# OpenHPI_Embedded_Smart_Home_RPi_Board.net
KiCad netlist of a schematic drawn in EAGLE
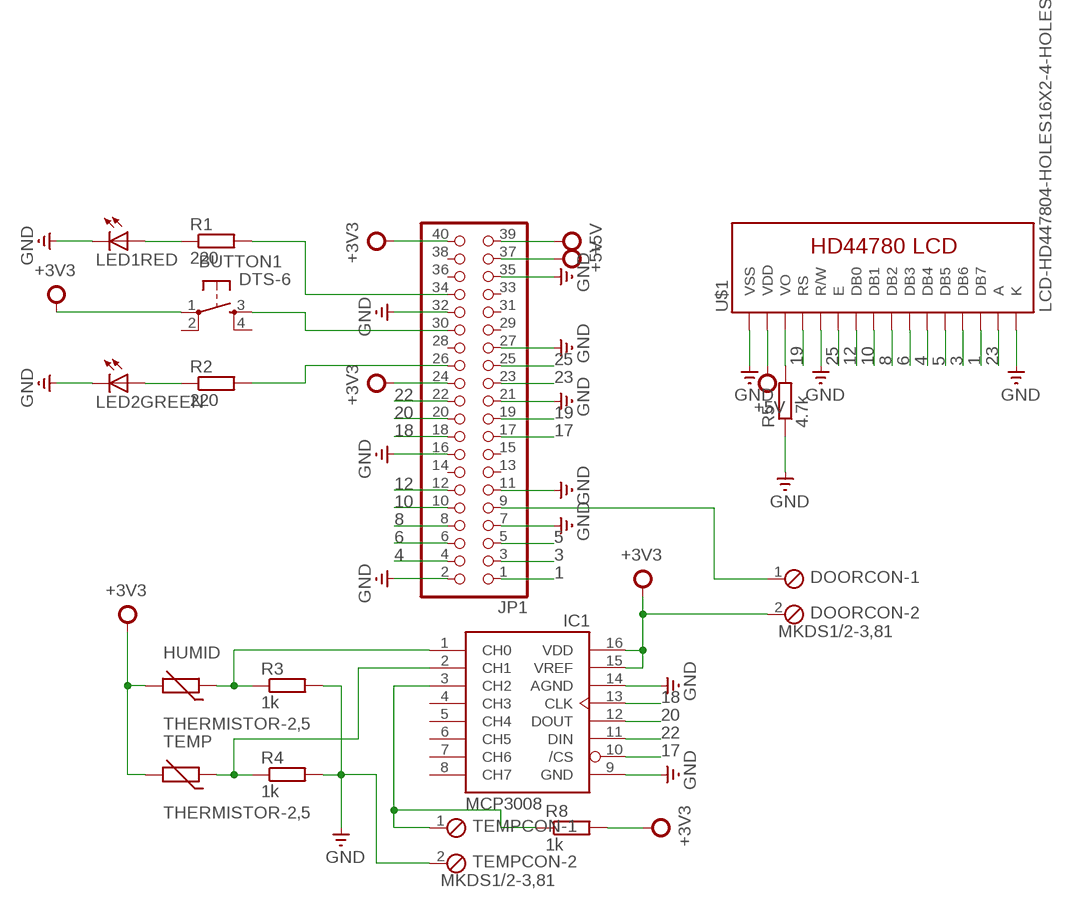
[diagram p0: schematic, sheet 1]

(export (version "E")
  (design (tool "Eeschema 10.0.6"))
  (components
    (comp (ref "BUTTON1")
      (value "DTS-6")
      (footprint "eagle-import:DTS-6")
      (libsource (lib "eagle-import") (part "DTS-6"))
    )
    (comp (ref "DOORCON")
      (value "MKDS1/2-3,81")
      (footprint "eagle-import:2POL381")
      (libsource (lib "eagle-import") (part "MKDS1/2-3,81"))
    )
    (comp (ref "HUMID")
      (value "THERMISTOR-2,5")
      (footprint "eagle-import:RS-2,5")
      (libsource (lib "eagle-import") (part "THERMISTOR-2,5"))
    )
    (comp (ref "IC1")
      (value "MCP3008")
      (footprint "eagle-import:DIL16")
      (libsource (lib "eagle-import") (part "MCP3008"))
    )
    (comp (ref "JP1")
      (value "PINHD-2X20")
      (footprint "eagle-import:2X20")
      (libsource (lib "eagle-import") (part "PINHD-2X20"))
    )
    (comp (ref "LED1RED")
      (value "LED5MM")
      (footprint "eagle-import:LED5MM")
      (libsource (lib "eagle-import") (part "LED5MM"))
    )
    (comp (ref "LED2GREEN")
      (value "LED5MM")
      (footprint "eagle-import:LED5MM")
      (libsource (lib "eagle-import") (part "LED5MM"))
    )
    (comp (ref "R1")
      (value "220")
      (footprint "eagle-import:0207_7")
      (libsource (lib "eagle-import") (part "R-EU_0207/7"))
    )
    (comp (ref "R2")
      (value "220")
      (footprint "eagle-import:0207_7")
      (libsource (lib "eagle-import") (part "R-EU_0207/7"))
    )
    (comp (ref "R3")
      (value "1k")
      (footprint "eagle-import:0207_7")
      (libsource (lib "eagle-import") (part "R-EU_0207/7"))
    )
    (comp (ref "R4")
      (value "1k")
      (footprint "eagle-import:0207_7")
      (libsource (lib "eagle-import") (part "R-EU_0207/7"))
    )
    (comp (ref "R5")
      (value "4.7k")
      (footprint "eagle-import:0207_7")
      (libsource (lib "eagle-import") (part "R-EU_0207/7"))
    )
    (comp (ref "R8")
      (value "1k")
      (footprint "eagle-import:0207_7")
      (libsource (lib "eagle-import") (part "R-EU_0207/7"))
    )
    (comp (ref "TEMP")
      (value "THERMISTOR-2,5")
      (footprint "eagle-import:RS-2,5")
      (libsource (lib "eagle-import") (part "THERMISTOR-2,5"))
    )
    (comp (ref "TEMPCON")
      (value "MKDS1/2-3,81")
      (footprint "eagle-import:2POL381")
      (libsource (lib "eagle-import") (part "MKDS1/2-3,81"))
    )
    (comp (ref "U$1")
      (value "LCD-HD447804-HOLES16X2-4-HOLES")
      (footprint "eagle-import:LCD-16X2-4HOLES")
      (libsource (lib "eagle-import") (part "LCD-HD4478016X2-4-HOLES4-HOLES"))
    )
  )
  (nets
    (net (code "1") (name "+3V3") (class "Default")
      (node (ref "BUTTON1") (pin "1") (pinfunction "1_1") (pintype "passive"))
      (node (ref "DOORCON") (pin "2") (pinfunction "1_2") (pintype "passive"))
      (node (ref "HUMID") (pin "2") (pinfunction "2_2") (pintype "passive"))
      (node (ref "IC1") (pin "15") (pinfunction "VREF_15") (pintype "input"))
      (node (ref "IC1") (pin "16") (pinfunction "VDD_16") (pintype "power_in"))
      (node (ref "JP1") (pin "24") (pinfunction "24_24") (pintype "passive"))
      (node (ref "JP1") (pin "40") (pinfunction "40_40") (pintype "passive"))
      (node (ref "R8") (pin "2") (pinfunction "2_2") (pintype "passive"))
      (node (ref "TEMP") (pin "2") (pinfunction "2_2") (pintype "passive"))
    )
    (net (code "2") (name "+5V") (class "Default")
      (node (ref "JP1") (pin "37") (pinfunction "37_37") (pintype "passive"))
      (node (ref "JP1") (pin "39") (pinfunction "39_39") (pintype "passive"))
      (node (ref "U$1") (pin "2") (pinfunction "VDD_2") (pintype "power_in"))
    )
    (net (code "3") (name "/1") (class "Default")
      (node (ref "JP1") (pin "1") (pinfunction "1_1") (pintype "passive"))
      (node (ref "U$1") (pin "14") (pinfunction "DB7_14") (pintype "bidirectional"))
    )
    (net (code "4") (name "/3") (class "Default")
      (node (ref "JP1") (pin "3") (pinfunction "3_3") (pintype "passive"))
      (node (ref "U$1") (pin "13") (pinfunction "DB6_13") (pintype "bidirectional"))
    )
    (net (code "5") (name "/4") (class "Default")
      (node (ref "JP1") (pin "4") (pinfunction "4_4") (pintype "passive"))
      (node (ref "U$1") (pin "11") (pinfunction "DB4_11") (pintype "bidirectional"))
    )
    (net (code "6") (name "/5") (class "Default")
      (node (ref "JP1") (pin "5") (pinfunction "5_5") (pintype "passive"))
      (node (ref "U$1") (pin "12") (pinfunction "DB5_12") (pintype "bidirectional"))
    )
    (net (code "7") (name "/6") (class "Default")
      (node (ref "JP1") (pin "6") (pinfunction "6_6") (pintype "passive"))
      (node (ref "U$1") (pin "10") (pinfunction "DB3_10") (pintype "bidirectional"))
    )
    (net (code "8") (name "/8") (class "Default")
      (node (ref "JP1") (pin "8") (pinfunction "8_8") (pintype "passive"))
      (node (ref "U$1") (pin "9") (pinfunction "DB2_9") (pintype "bidirectional"))
    )
    (net (code "9") (name "/10") (class "Default")
      (node (ref "JP1") (pin "10") (pinfunction "10_10") (pintype "passive"))
      (node (ref "U$1") (pin "8") (pinfunction "DB1_8") (pintype "bidirectional"))
    )
    (net (code "10") (name "/12") (class "Default")
      (node (ref "JP1") (pin "12") (pinfunction "12_12") (pintype "passive"))
      (node (ref "U$1") (pin "7") (pinfunction "DB0_7") (pintype "bidirectional"))
    )
    (net (code "11") (name "/17") (class "Default")
      (node (ref "IC1") (pin "10") (pinfunction "/CS_10") (pintype "input"))
      (node (ref "JP1") (pin "17") (pinfunction "17_17") (pintype "passive"))
    )
    (net (code "12") (name "/18") (class "Default")
      (node (ref "IC1") (pin "13") (pinfunction "CLK_13") (pintype "input"))
      (node (ref "JP1") (pin "18") (pinfunction "18_18") (pintype "passive"))
    )
    (net (code "13") (name "/19") (class "Default")
      (node (ref "JP1") (pin "19") (pinfunction "19_19") (pintype "passive"))
      (node (ref "U$1") (pin "4") (pinfunction "RS_4") (pintype "input"))
    )
    (net (code "14") (name "/20") (class "Default")
      (node (ref "IC1") (pin "12") (pinfunction "DOUT_12") (pintype "output"))
      (node (ref "JP1") (pin "20") (pinfunction "20_20") (pintype "passive"))
    )
    (net (code "15") (name "/22") (class "Default")
      (node (ref "IC1") (pin "11") (pinfunction "DIN_11") (pintype "input"))
      (node (ref "JP1") (pin "22") (pinfunction "22_22") (pintype "passive"))
    )
    (net (code "16") (name "/23") (class "Default")
      (node (ref "JP1") (pin "23") (pinfunction "23_23") (pintype "passive"))
      (node (ref "U$1") (pin "15") (pinfunction "A_15") (pintype "power_in"))
    )
    (net (code "17") (name "/25") (class "Default")
      (node (ref "JP1") (pin "25") (pinfunction "25_25") (pintype "passive"))
      (node (ref "U$1") (pin "6") (pinfunction "E_6") (pintype "input"))
    )
    (net (code "18") (name "GND") (class "Default")
      (node (ref "IC1") (pin "14") (pinfunction "AGND_14") (pintype "power_in"))
      (node (ref "IC1") (pin "9") (pinfunction "GND_9") (pintype "power_in"))
      (node (ref "JP1") (pin "11") (pinfunction "11_11") (pintype "passive"))
      (node (ref "JP1") (pin "16") (pinfunction "16_16") (pintype "passive"))
      (node (ref "JP1") (pin "2") (pinfunction "2_2") (pintype "passive"))
      (node (ref "JP1") (pin "21") (pinfunction "21_21") (pintype "passive"))
      (node (ref "JP1") (pin "27") (pinfunction "27_27") (pintype "passive"))
      (node (ref "JP1") (pin "32") (pinfunction "32_32") (pintype "passive"))
      (node (ref "JP1") (pin "35") (pinfunction "35_35") (pintype "passive"))
      (node (ref "JP1") (pin "7") (pinfunction "7_7") (pintype "passive"))
      (node (ref "LED1RED") (pin "K") (pinfunction "C_K") (pintype "passive"))
      (node (ref "LED2GREEN") (pin "K") (pinfunction "C_K") (pintype "passive"))
      (node (ref "R3") (pin "2") (pinfunction "2_2") (pintype "passive"))
      (node (ref "R4") (pin "2") (pinfunction "2_2") (pintype "passive"))
      (node (ref "R5") (pin "1") (pinfunction "1_1") (pintype "passive"))
      (node (ref "TEMPCON") (pin "2") (pinfunction "1_2") (pintype "passive"))
      (node (ref "U$1") (pin "1") (pinfunction "VSS_1") (pintype "power_in"))
      (node (ref "U$1") (pin "16") (pinfunction "K_16") (pintype "power_in"))
      (node (ref "U$1") (pin "5") (pinfunction "R/W_5") (pintype "input"))
    )
    (net (code "19") (name "Net-(BUTTON1-Pad3)") (class "Default")
      (node (ref "BUTTON1") (pin "3") (pinfunction "3_3") (pintype "passive"))
      (node (ref "JP1") (pin "30") (pinfunction "30_30") (pintype "passive"))
    )
    (net (code "20") (name "Net-(DOORCON-Pad1)") (class "Default")
      (node (ref "DOORCON") (pin "1") (pinfunction "1_1") (pintype "passive"))
      (node (ref "JP1") (pin "9") (pinfunction "9_9") (pintype "passive"))
    )
    (net (code "21") (name "Net-(IC1-CH0)") (class "Default")
      (node (ref "HUMID") (pin "1") (pinfunction "1_1") (pintype "passive"))
      (node (ref "IC1") (pin "1") (pinfunction "CH0_1") (pintype "input"))
      (node (ref "R3") (pin "1") (pinfunction "1_1") (pintype "passive"))
    )
    (net (code "22") (name "Net-(IC1-CH1)") (class "Default")
      (node (ref "IC1") (pin "2") (pinfunction "CH1_2") (pintype "input"))
      (node (ref "R4") (pin "1") (pinfunction "1_1") (pintype "passive"))
      (node (ref "TEMP") (pin "1") (pinfunction "1_1") (pintype "passive"))
    )
    (net (code "23") (name "Net-(IC1-CH2)") (class "Default")
      (node (ref "IC1") (pin "3") (pinfunction "CH2_3") (pintype "input"))
      (node (ref "R8") (pin "1") (pinfunction "1_1") (pintype "passive"))
      (node (ref "TEMPCON") (pin "1") (pinfunction "1_1") (pintype "passive"))
    )
    (net (code "24") (name "Net-(JP1-Pad26)") (class "Default")
      (node (ref "JP1") (pin "26") (pinfunction "26_26") (pintype "passive"))
      (node (ref "R2") (pin "2") (pinfunction "2_2") (pintype "passive"))
    )
    (net (code "25") (name "Net-(JP1-Pad34)") (class "Default")
      (node (ref "JP1") (pin "34") (pinfunction "34_34") (pintype "passive"))
      (node (ref "R1") (pin "2") (pinfunction "2_2") (pintype "passive"))
    )
    (net (code "26") (name "Net-(LED1RED-PadA)") (class "Default")
      (node (ref "LED1RED") (pin "A") (pinfunction "A_A") (pintype "passive"))
      (node (ref "R1") (pin "1") (pinfunction "1_1") (pintype "passive"))
    )
    (net (code "27") (name "Net-(LED2GREEN-PadA)") (class "Default")
      (node (ref "LED2GREEN") (pin "A") (pinfunction "A_A") (pintype "passive"))
      (node (ref "R2") (pin "1") (pinfunction "1_1") (pintype "passive"))
    )
    (net (code "28") (name "Net-(U$1-VO)") (class "Default")
      (node (ref "R5") (pin "2") (pinfunction "2_2") (pintype "passive"))
      (node (ref "U$1") (pin "3") (pinfunction "VO_3") (pintype "bidirectional"))
    )
    (net (code "29") (name "unconnected-(BUTTON1-Pad2)") (class "Default")
      (node (ref "BUTTON1") (pin "2") (pinfunction "2_2") (pintype "passive"))
    )
    (net (code "30") (name "unconnected-(BUTTON1-Pad4)") (class "Default")
      (node (ref "BUTTON1") (pin "4") (pinfunction "4_4") (pintype "passive"))
    )
    (net (code "31") (name "unconnected-(IC1-CH3-Pad4)") (class "Default")
      (node (ref "IC1") (pin "4") (pinfunction "CH3_4") (pintype "input"))
    )
    (net (code "32") (name "unconnected-(IC1-CH4-Pad5)") (class "Default")
      (node (ref "IC1") (pin "5") (pinfunction "CH4_5") (pintype "input"))
    )
    (net (code "33") (name "unconnected-(IC1-CH5-Pad6)") (class "Default")
      (node (ref "IC1") (pin "6") (pinfunction "CH5_6") (pintype "input"))
    )
    (net (code "34") (name "unconnected-(IC1-CH6-Pad7)") (class "Default")
      (node (ref "IC1") (pin "7") (pinfunction "CH6_7") (pintype "input"))
    )
    (net (code "35") (name "unconnected-(IC1-CH7-Pad8)") (class "Default")
      (node (ref "IC1") (pin "8") (pinfunction "CH7_8") (pintype "input"))
    )
    (net (code "36") (name "unconnected-(JP1-Pad13)") (class "Default")
      (node (ref "JP1") (pin "13") (pinfunction "13_13") (pintype "passive"))
    )
    (net (code "37") (name "unconnected-(JP1-Pad14)") (class "Default")
      (node (ref "JP1") (pin "14") (pinfunction "14_14") (pintype "passive"))
    )
    (net (code "38") (name "unconnected-(JP1-Pad15)") (class "Default")
      (node (ref "JP1") (pin "15") (pinfunction "15_15") (pintype "passive"))
    )
    (net (code "39") (name "unconnected-(JP1-Pad28)") (class "Default")
      (node (ref "JP1") (pin "28") (pinfunction "28_28") (pintype "passive"))
    )
    (net (code "40") (name "unconnected-(JP1-Pad29)") (class "Default")
      (node (ref "JP1") (pin "29") (pinfunction "29_29") (pintype "passive"))
    )
    (net (code "41") (name "unconnected-(JP1-Pad31)") (class "Default")
      (node (ref "JP1") (pin "31") (pinfunction "31_31") (pintype "passive"))
    )
    (net (code "42") (name "unconnected-(JP1-Pad33)") (class "Default")
      (node (ref "JP1") (pin "33") (pinfunction "33_33") (pintype "passive"))
    )
    (net (code "43") (name "unconnected-(JP1-Pad36)") (class "Default")
      (node (ref "JP1") (pin "36") (pinfunction "36_36") (pintype "passive"))
    )
    (net (code "44") (name "unconnected-(JP1-Pad38)") (class "Default")
      (node (ref "JP1") (pin "38") (pinfunction "38_38") (pintype "passive"))
    )
  )
)
